# SZG-TEMPLATE-STD.net
KiCad netlist of a schematic drawn in Altium Designer
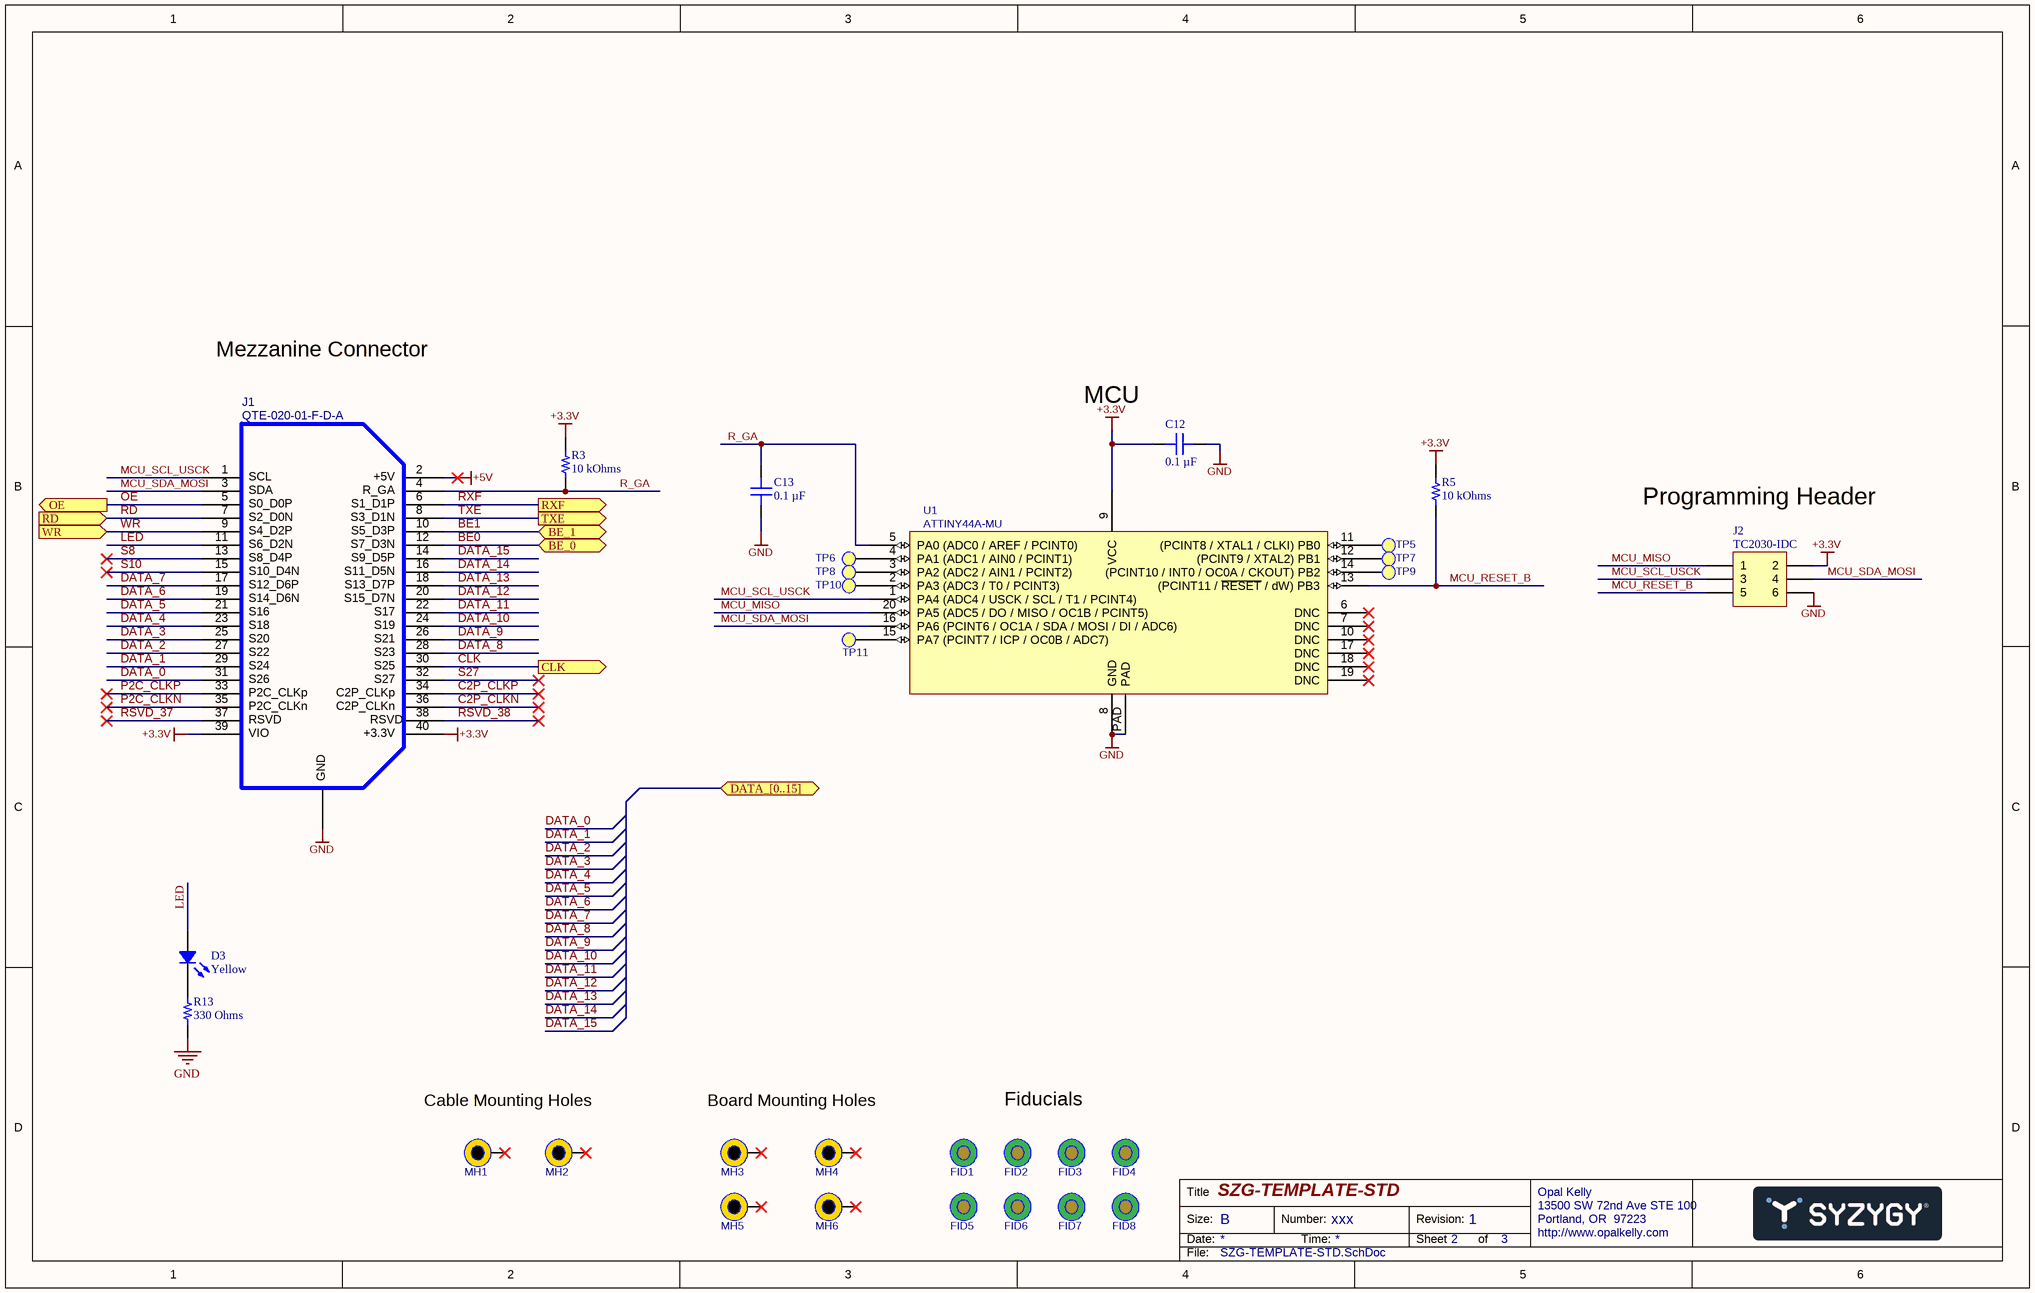
[diagram p0: SZG-TEMPLATE-STD.SchDoc]

(export (version "E")
  (design (tool "Eeschema 10.0.6"))
  (components
    (comp (ref "C12")
      (value "0.1 µF")
      (footprint "CAP 0201_0603")
      (description "CAP CER 0.1UF 16V X5R 0201")
      (fields (field (name "PART NUMBER") "EMK063BJ104KP-F") (field (name "MANUFACTURER") "Taiyo Yuden"))
      (libsource (lib "Celestial Altium Library - altium_library") (part "Capacitor"))
    )
    (comp (ref "C13")
      (value "0.1 µF")
      (footprint "CAP 0201_0603")
      (description "CAP CER 0.1UF 16V X5R 0201")
      (fields (field (name "PART NUMBER") "EMK063BJ104KP-F") (field (name "MANUFACTURER") "Taiyo Yuden"))
      (libsource (lib "Celestial Altium Library - altium_library") (part "Capacitor"))
    )
    (comp (ref "D3")
      (value "Yellow")
      (footprint "LED 1206_3216 YELLOW")
      (description "LED YELLOW CLEAR 1206 SMD")
      (fields
        (field (name "PART NUMBER") "CMD11-21VYC/TR8")
        (field (name "MANUFACTURER") "Visual Communications Company - VCC")
      )
      (libsource (lib "Celestial Altium Library - altium_library") (part "LED"))
    )
    (comp (ref "FID1")
      (value "FIDUCIAL")
      (footprint "FID1MM/2MM-SS")
      (description "PCB fiducial")
      (libsource (lib "NoBOM") (part "FIDUCIAL"))
    )
    (comp (ref "FID2")
      (value "FIDUCIAL")
      (footprint "FID1MM/2MM-SS")
      (description "PCB fiducial")
      (libsource (lib "NoBOM") (part "FIDUCIAL"))
    )
    (comp (ref "FID3")
      (value "FIDUCIAL")
      (footprint "FID1MM/2MM-SS")
      (description "PCB fiducial")
      (libsource (lib "NoBOM") (part "FIDUCIAL"))
    )
    (comp (ref "FID4")
      (value "FIDUCIAL")
      (footprint "FID1MM/2MM-SS")
      (description "PCB fiducial")
      (libsource (lib "NoBOM") (part "FIDUCIAL"))
    )
    (comp (ref "FID5")
      (value "FIDUCIAL")
      (footprint "FID1MM/2MM-SS")
      (description "PCB fiducial")
      (libsource (lib "NoBOM") (part "FIDUCIAL"))
    )
    (comp (ref "FID6")
      (value "FIDUCIAL")
      (footprint "FID1MM/2MM-SS")
      (description "PCB fiducial")
      (libsource (lib "NoBOM") (part "FIDUCIAL"))
    )
    (comp (ref "FID7")
      (value "FIDUCIAL")
      (footprint "FID1MM/2MM-SS")
      (description "PCB fiducial")
      (libsource (lib "NoBOM") (part "FIDUCIAL"))
    )
    (comp (ref "FID8")
      (value "FIDUCIAL")
      (footprint "FID1MM/2MM-SS")
      (description "PCB fiducial")
      (libsource (lib "NoBOM") (part "FIDUCIAL"))
    )
    (comp (ref "J1")
      (value "QTE-020-01-F-D-A")
      (footprint "QTE-020-01-X-D-A-L")
      (fields (field (name "PARTNUMBER") "000973") (field (name "MANUFACTURER") "Samtec"))
      (libsource (lib "Aligni") (part "QTE_QSE-020"))
    )
    (comp (ref "J2")
      (value "~")
      (footprint "TC2030-DUAL")
      (description "Tag-Connect 6-pin Plug-of-Nails spring-pin cable footprint")
      (fields
        (field (name "ALIGNIPARTNUMBER") "002062")
        (field (name "MANUFACTURER") "Tag-Connect")
        (field (name "MANUFACTURER_PN") "TC2030-IDC")
      )
      (libsource (lib "Aligni") (part "Header 3X2"))
    )
    (comp (ref "MH1")
      (value "MTG")
      (footprint "MTG-3.2/6.5-PTH")
      (description "Mounting hole")
      (libsource (lib "NoBOM") (part "MTG"))
    )
    (comp (ref "MH2")
      (value "MTG")
      (footprint "MTG-3.2/6.5-PTH")
      (description "Mounting hole")
      (libsource (lib "NoBOM") (part "MTG"))
    )
    (comp (ref "MH3")
      (value "MTG")
      (footprint "MTG-3.2/6.5-PTH")
      (description "Mounting hole")
      (libsource (lib "NoBOM") (part "MTG"))
    )
    (comp (ref "MH4")
      (value "MTG")
      (footprint "MTG-3.2/6.5-PTH")
      (description "Mounting hole")
      (libsource (lib "NoBOM") (part "MTG"))
    )
    (comp (ref "MH5")
      (value "MTG")
      (footprint "MTG-3.2/6.5-PTH")
      (description "Mounting hole")
      (libsource (lib "NoBOM") (part "MTG"))
    )
    (comp (ref "MH6")
      (value "MTG")
      (footprint "MTG-3.2/6.5-PTH")
      (description "Mounting hole")
      (libsource (lib "NoBOM") (part "MTG"))
    )
    (comp (ref "R3")
      (value "10 kOhms")
      (footprint "RES 0201_0603")
      (description "RES SMD 10K OHM 1% 1/20W 0201")
      (fields (field (name "PART NUMBER") "CRCW020110K0FKED") (field (name "MANUFACTURER") "Vishay Dale"))
      (libsource (lib "Celestial Altium Library - altium_library") (part "Resistor"))
    )
    (comp (ref "R5")
      (value "10 kOhms")
      (footprint "RES 0201_0603")
      (description "RES SMD 10K OHM 1% 1/20W 0201")
      (fields (field (name "PART NUMBER") "CRCW020110K0FKED") (field (name "MANUFACTURER") "Vishay Dale"))
      (libsource (lib "Celestial Altium Library - altium_library") (part "Resistor"))
    )
    (comp (ref "R13")
      (value "330 Ohms")
      (footprint "RES 0603_1608")
      (description "RESHIGHPOWERA 0603 330R 1% 1/4W")
      (fields (field (name "PART NUMBER") "CMP0603AFX-3300ELF") (field (name "MANUFACTURER") "Bourns Inc."))
      (libsource (lib "Celestial Altium Library - altium_library") (part "Resistor"))
    )
    (comp (ref "TP5")
      (value "TESTPOINT-SMD20")
      (footprint "TP-SMD20")
      (description "Test point, surface-mount, 20mil")
      (libsource (lib "NoBOM") (part "TESTPOINT-SMD20"))
    )
    (comp (ref "TP6")
      (value "TESTPOINT-SMD20")
      (footprint "TP-SMD20")
      (description "Test point, surface-mount, 20mil")
      (libsource (lib "NoBOM") (part "TESTPOINT-SMD20"))
    )
    (comp (ref "TP7")
      (value "TESTPOINT-SMD20")
      (footprint "TP-SMD20")
      (description "Test point, surface-mount, 20mil")
      (libsource (lib "NoBOM") (part "TESTPOINT-SMD20"))
    )
    (comp (ref "TP8")
      (value "TESTPOINT-SMD20")
      (footprint "TP-SMD20")
      (description "Test point, surface-mount, 20mil")
      (libsource (lib "NoBOM") (part "TESTPOINT-SMD20"))
    )
    (comp (ref "TP9")
      (value "TESTPOINT-SMD20")
      (footprint "TP-SMD20")
      (description "Test point, surface-mount, 20mil")
      (libsource (lib "NoBOM") (part "TESTPOINT-SMD20"))
    )
    (comp (ref "TP10")
      (value "TESTPOINT-SMD20")
      (footprint "TP-SMD20")
      (description "Test point, surface-mount, 20mil")
      (libsource (lib "NoBOM") (part "TESTPOINT-SMD20"))
    )
    (comp (ref "TP11")
      (value "TESTPOINT-SMD20")
      (footprint "TP-SMD20")
      (description "Test point, surface-mount, 20mil")
      (libsource (lib "NoBOM") (part "TESTPOINT-SMD20"))
    )
    (comp (ref "U1")
      (value "ATTINY44A-MU")
      (footprint "QFN-EP-20")
      (description "8-bit MCU, 4 KB flash, 256 bytes EEPROM")
      (fields (field (name "MANUFACTURER") "Microchip") (field (name "PARTNUMBER") "001552"))
      (libsource (lib "Aligni") (part "ATTINYx4A-MU"))
    )
  )
  (nets
    (net (code "1") (name "+3.3V") (class "Default")
      (node (ref "C12") (pin "1") (pinfunction "1_1") (pintype "passive"))
      (node (ref "J1") (pin "39") (pinfunction "39_39") (pintype "passive"))
      (node (ref "J1") (pin "40") (pinfunction "40_40") (pintype "passive"))
      (node (ref "J2") (pin "2") (pinfunction "2_2") (pintype "passive"))
      (node (ref "R3") (pin "2") (pinfunction "2_2") (pintype "passive"))
      (node (ref "R5") (pin "2") (pinfunction "2_2") (pintype "passive"))
      (node (ref "U1") (pin "9") (pinfunction "VCC_9") (pintype "power_in"))
    )
    (net (code "2") (name "+5V") (class "Default")
      (node (ref "J1") (pin "2") (pinfunction "2_2") (pintype "passive"))
    )
    (net (code "3") (name "/BE0") (class "Default")
      (node (ref "J1") (pin "12") (pinfunction "12_12") (pintype "passive"))
    )
    (net (code "4") (name "/BE1") (class "Default")
      (node (ref "J1") (pin "10") (pinfunction "10_10") (pintype "passive"))
    )
    (net (code "5") (name "/C2P_CLKN") (class "Default")
      (node (ref "J1") (pin "36") (pinfunction "36_36") (pintype "passive+no_connect"))
    )
    (net (code "6") (name "/C2P_CLKP") (class "Default")
      (node (ref "J1") (pin "34") (pinfunction "34_34") (pintype "passive+no_connect"))
    )
    (net (code "7") (name "/CLK") (class "Default")
      (node (ref "J1") (pin "30") (pinfunction "30_30") (pintype "passive"))
    )
    (net (code "8") (name "/DATA_0") (class "Default")
      (node (ref "J1") (pin "31") (pinfunction "31_31") (pintype "passive"))
    )
    (net (code "9") (name "/DATA_1") (class "Default")
      (node (ref "J1") (pin "29") (pinfunction "29_29") (pintype "passive"))
    )
    (net (code "10") (name "/DATA_2") (class "Default")
      (node (ref "J1") (pin "27") (pinfunction "27_27") (pintype "passive"))
    )
    (net (code "11") (name "/DATA_3") (class "Default")
      (node (ref "J1") (pin "25") (pinfunction "25_25") (pintype "passive"))
    )
    (net (code "12") (name "/DATA_4") (class "Default")
      (node (ref "J1") (pin "23") (pinfunction "23_23") (pintype "passive"))
    )
    (net (code "13") (name "/DATA_5") (class "Default")
      (node (ref "J1") (pin "21") (pinfunction "21_21") (pintype "passive"))
    )
    (net (code "14") (name "/DATA_6") (class "Default")
      (node (ref "J1") (pin "19") (pinfunction "19_19") (pintype "passive"))
    )
    (net (code "15") (name "/DATA_7") (class "Default")
      (node (ref "J1") (pin "17") (pinfunction "17_17") (pintype "passive"))
    )
    (net (code "16") (name "/DATA_8") (class "Default")
      (node (ref "J1") (pin "28") (pinfunction "28_28") (pintype "passive"))
    )
    (net (code "17") (name "/DATA_9") (class "Default")
      (node (ref "J1") (pin "26") (pinfunction "26_26") (pintype "passive"))
    )
    (net (code "18") (name "/DATA_10") (class "Default")
      (node (ref "J1") (pin "24") (pinfunction "24_24") (pintype "passive"))
    )
    (net (code "19") (name "/DATA_11") (class "Default")
      (node (ref "J1") (pin "22") (pinfunction "22_22") (pintype "passive"))
    )
    (net (code "20") (name "/DATA_12") (class "Default")
      (node (ref "J1") (pin "20") (pinfunction "20_20") (pintype "passive"))
    )
    (net (code "21") (name "/DATA_13") (class "Default")
      (node (ref "J1") (pin "18") (pinfunction "18_18") (pintype "passive"))
    )
    (net (code "22") (name "/DATA_14") (class "Default")
      (node (ref "J1") (pin "16") (pinfunction "16_16") (pintype "passive"))
    )
    (net (code "23") (name "/DATA_15") (class "Default")
      (node (ref "J1") (pin "14") (pinfunction "14_14") (pintype "passive"))
    )
    (net (code "25") (name "/LED") (class "Default")
      (node (ref "D3") (pin "1") (pinfunction "1_1") (pintype "passive"))
      (node (ref "J1") (pin "11") (pinfunction "11_11") (pintype "passive"))
    )
    (net (code "26") (name "/MCU_MISO") (class "Default")
      (node (ref "J2") (pin "1") (pinfunction "1_1") (pintype "passive"))
      (node (ref "U1") (pin "20") (pinfunction "PA5_(ADC5_/_DO_/_MISO_/_OC1B_/_PCINT5)_20") (pintype "bidirectional"))
    )
    (net (code "27") (name "/MCU_RESET_B") (class "Default")
      (node (ref "J2") (pin "5") (pinfunction "5_5") (pintype "passive"))
      (node (ref "R5") (pin "1") (pinfunction "1_1") (pintype "passive"))
      (node (ref "U1") (pin "13") (pinfunction "(PCINT11_/_~{RESET}_/_dW)_PB3_13") (pintype "bidirectional"))
    )
    (net (code "28") (name "/MCU_SCL_USCK") (class "Default")
      (node (ref "J1") (pin "1") (pinfunction "1_1") (pintype "passive"))
      (node (ref "J2") (pin "3") (pinfunction "3_3") (pintype "passive"))
      (node (ref "U1") (pin "1") (pinfunction "PA4_(ADC4_/_USCK_/_SCL_/_T1_/_PCINT4)_1") (pintype "bidirectional"))
    )
    (net (code "29") (name "/MCU_SDA_MOSI") (class "Default")
      (node (ref "J1") (pin "3") (pinfunction "3_3") (pintype "passive"))
      (node (ref "J2") (pin "4") (pinfunction "4_4") (pintype "passive"))
      (node (ref "U1") (pin "16") (pinfunction "PA6_(PCINT6_/_OC1A_/_SDA_/_MOSI_/_DI_/_ADC6)_16") (pintype "bidirectional"))
    )
    (net (code "30") (name "/OE") (class "Default")
      (node (ref "J1") (pin "5") (pinfunction "5_5") (pintype "passive"))
    )
    (net (code "31") (name "/P2C_CLKN") (class "Default")
      (node (ref "J1") (pin "35") (pinfunction "35_35") (pintype "passive+no_connect"))
    )
    (net (code "32") (name "/P2C_CLKP") (class "Default")
      (node (ref "J1") (pin "33") (pinfunction "33_33") (pintype "passive+no_connect"))
    )
    (net (code "33") (name "/RD") (class "Default")
      (node (ref "J1") (pin "7") (pinfunction "7_7") (pintype "passive"))
    )
    (net (code "34") (name "/RSVD_37") (class "Default")
      (node (ref "J1") (pin "37") (pinfunction "37_37") (pintype "passive+no_connect"))
    )
    (net (code "35") (name "/RSVD_38") (class "Default")
      (node (ref "J1") (pin "38") (pinfunction "38_38") (pintype "passive+no_connect"))
    )
    (net (code "36") (name "/RXF") (class "Default")
      (node (ref "J1") (pin "6") (pinfunction "6_6") (pintype "passive"))
    )
    (net (code "37") (name "/R_GA") (class "Default")
      (node (ref "C13") (pin "2") (pinfunction "2_2") (pintype "passive"))
      (node (ref "J1") (pin "4") (pinfunction "4_4") (pintype "passive"))
      (node (ref "R3") (pin "1") (pinfunction "1_1") (pintype "passive"))
      (node (ref "U1") (pin "5") (pinfunction "PA0_(ADC0_/_AREF_/_PCINT0)_5") (pintype "bidirectional"))
    )
    (net (code "38") (name "/S8") (class "Default")
      (node (ref "J1") (pin "13") (pinfunction "13_13") (pintype "passive+no_connect"))
    )
    (net (code "39") (name "/S10") (class "Default")
      (node (ref "J1") (pin "15") (pinfunction "15_15") (pintype "passive+no_connect"))
    )
    (net (code "40") (name "/S27") (class "Default")
      (node (ref "J1") (pin "32") (pinfunction "32_32") (pintype "passive+no_connect"))
    )
    (net (code "41") (name "/TXE") (class "Default")
      (node (ref "J1") (pin "8") (pinfunction "8_8") (pintype "passive"))
    )
    (net (code "42") (name "/WR") (class "Default")
      (node (ref "J1") (pin "9") (pinfunction "9_9") (pintype "passive"))
    )
    (net (code "43") (name "GND") (class "Default")
      (node (ref "C12") (pin "2") (pinfunction "2_2") (pintype "passive"))
      (node (ref "C13") (pin "1") (pinfunction "1_1") (pintype "passive"))
      (node (ref "J1") (pin "0") (pinfunction "0_0") (pintype "passive"))
      (node (ref "J2") (pin "6") (pinfunction "6_6") (pintype "passive"))
      (node (ref "R13") (pin "1") (pinfunction "1_1") (pintype "passive"))
      (node (ref "U1") (pin "8") (pinfunction "GND_8") (pintype "power_in"))
      (node (ref "U1") (pin "PAD") (pinfunction "PAD_PAD") (pintype "power_in"))
    )
    (net (code "44") (name "Net-(D3-Pad2)") (class "Default")
      (node (ref "D3") (pin "2") (pinfunction "2_2") (pintype "passive"))
      (node (ref "R13") (pin "2") (pinfunction "2_2") (pintype "passive"))
    )
    (net (code "45") (name "Net-(TP5-PIN)") (class "Default")
      (node (ref "TP5") (pin "1") (pinfunction "PIN_1") (pintype "passive"))
      (node (ref "U1") (pin "11") (pinfunction "(PCINT8_/_XTAL1_/_CLKI)_PB0_11") (pintype "bidirectional"))
    )
    (net (code "46") (name "Net-(TP6-PIN)") (class "Default")
      (node (ref "TP6") (pin "1") (pinfunction "PIN_1") (pintype "passive"))
      (node (ref "U1") (pin "4") (pinfunction "PA1_(ADC1_/_AIN0_/_PCINT1)_4") (pintype "bidirectional"))
    )
    (net (code "47") (name "Net-(TP7-PIN)") (class "Default")
      (node (ref "TP7") (pin "1") (pinfunction "PIN_1") (pintype "passive"))
      (node (ref "U1") (pin "12") (pinfunction "(PCINT9_/_XTAL2)_PB1_12") (pintype "bidirectional"))
    )
    (net (code "48") (name "Net-(TP8-PIN)") (class "Default")
      (node (ref "TP8") (pin "1") (pinfunction "PIN_1") (pintype "passive"))
      (node (ref "U1") (pin "3") (pinfunction "PA2_(ADC2_/_AIN1_/_PCINT2)_3") (pintype "bidirectional"))
    )
    (net (code "49") (name "Net-(TP9-PIN)") (class "Default")
      (node (ref "TP9") (pin "1") (pinfunction "PIN_1") (pintype "passive"))
      (node (ref "U1") (pin "14") (pinfunction "(PCINT10_/_INT0_/_OC0A_/_CKOUT)_PB2_14") (pintype "bidirectional"))
    )
    (net (code "50") (name "Net-(TP10-PIN)") (class "Default")
      (node (ref "TP10") (pin "1") (pinfunction "PIN_1") (pintype "passive"))
      (node (ref "U1") (pin "2") (pinfunction "PA3_(ADC3_/_T0_/_PCINT3)_2") (pintype "bidirectional"))
    )
    (net (code "51") (name "Net-(TP11-PIN)") (class "Default")
      (node (ref "TP11") (pin "1") (pinfunction "PIN_1") (pintype "passive"))
      (node (ref "U1") (pin "15") (pinfunction "PA7_(PCINT7_/_ICP_/_OC0B_/_ADC7)_15") (pintype "bidirectional"))
    )
    (net (code "52") (name "unconnected-(MH1-Pad1)") (class "Default")
      (node (ref "MH1") (pin "1") (pinfunction "1_1") (pintype "passive+no_connect"))
    )
    (net (code "53") (name "unconnected-(MH2-Pad1)") (class "Default")
      (node (ref "MH2") (pin "1") (pinfunction "1_1") (pintype "passive+no_connect"))
    )
    (net (code "54") (name "unconnected-(MH3-Pad1)") (class "Default")
      (node (ref "MH3") (pin "1") (pinfunction "1_1") (pintype "passive+no_connect"))
    )
    (net (code "55") (name "unconnected-(MH4-Pad1)") (class "Default")
      (node (ref "MH4") (pin "1") (pinfunction "1_1") (pintype "passive+no_connect"))
    )
    (net (code "56") (name "unconnected-(MH5-Pad1)") (class "Default")
      (node (ref "MH5") (pin "1") (pinfunction "1_1") (pintype "passive+no_connect"))
    )
    (net (code "57") (name "unconnected-(MH6-Pad1)") (class "Default")
      (node (ref "MH6") (pin "1") (pinfunction "1_1") (pintype "passive+no_connect"))
    )
    (net (code "58") (name "unconnected-(U1-DNC-Pad6)") (class "Default")
      (node (ref "U1") (pin "6") (pinfunction "DNC_6") (pintype "passive+no_connect"))
    )
    (net (code "59") (name "unconnected-(U1-DNC-Pad7)") (class "Default")
      (node (ref "U1") (pin "7") (pinfunction "DNC_7") (pintype "passive+no_connect"))
    )
    (net (code "60") (name "unconnected-(U1-DNC-Pad10)") (class "Default")
      (node (ref "U1") (pin "10") (pinfunction "DNC_10") (pintype "passive+no_connect"))
    )
    (net (code "61") (name "unconnected-(U1-DNC-Pad17)") (class "Default")
      (node (ref "U1") (pin "17") (pinfunction "DNC_17") (pintype "passive+no_connect"))
    )
    (net (code "62") (name "unconnected-(U1-DNC-Pad18)") (class "Default")
      (node (ref "U1") (pin "18") (pinfunction "DNC_18") (pintype "passive+no_connect"))
    )
    (net (code "63") (name "unconnected-(U1-DNC-Pad19)") (class "Default")
      (node (ref "U1") (pin "19") (pinfunction "DNC_19") (pintype "passive+no_connect"))
    )
  )
)
